# motor.net
KiCad netlist of a schematic drawn in EAGLE
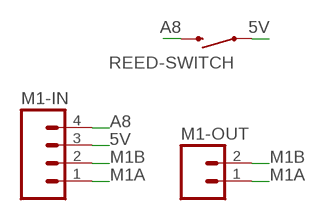
[diagram p0: schematic, sheet 1]

(export (version "E")
  (design (tool "Eeschema 10.0.6"))
  (components
    (comp (ref "M1-IN")
      (value "M04JST")
      (footprint "eagle-import:1X04-1.5MM_JST")
      (libsource (lib "eagle-import") (part "M04JST"))
    )
    (comp (ref "M1-OUT")
      (value "M02JST-PTH-2")
      (footprint "eagle-import:JST-2-PTH")
      (libsource (lib "eagle-import") (part "M02JST-PTH-2"))
    )
    (comp (ref "REED-SWITCH")
      (value "SWITCH-MOMENTARY-2PTH_REED2")
      (footprint "eagle-import:REED_SWITCH_PLASTIC")
      (libsource (lib "eagle-import") (part "SWITCH-MOMENTARY-2PTH_REED2"))
    )
  )
  (nets
    (net (code "1") (name "/5V") (class "Default")
      (node (ref "M1-IN") (pin "3") (pinfunction "3_3") (pintype "passive"))
      (node (ref "REED-SWITCH") (pin "P$1") (pinfunction "1_P$1") (pintype "passive"))
    )
    (net (code "2") (name "/A8") (class "Default")
      (node (ref "M1-IN") (pin "4") (pinfunction "4_4") (pintype "passive"))
      (node (ref "REED-SWITCH") (pin "P$2") (pinfunction "2_P$2") (pintype "passive"))
    )
    (net (code "3") (name "/M1A") (class "Default")
      (node (ref "M1-IN") (pin "1") (pinfunction "1_1") (pintype "passive"))
      (node (ref "M1-OUT") (pin "1") (pinfunction "1_1") (pintype "passive"))
    )
    (net (code "4") (name "/M1B") (class "Default")
      (node (ref "M1-IN") (pin "2") (pinfunction "2_2") (pintype "passive"))
      (node (ref "M1-OUT") (pin "2") (pinfunction "2_2") (pintype "passive"))
    )
  )
)
